# arduino_isp.net
KiCad netlist of a schematic drawn in EAGLE
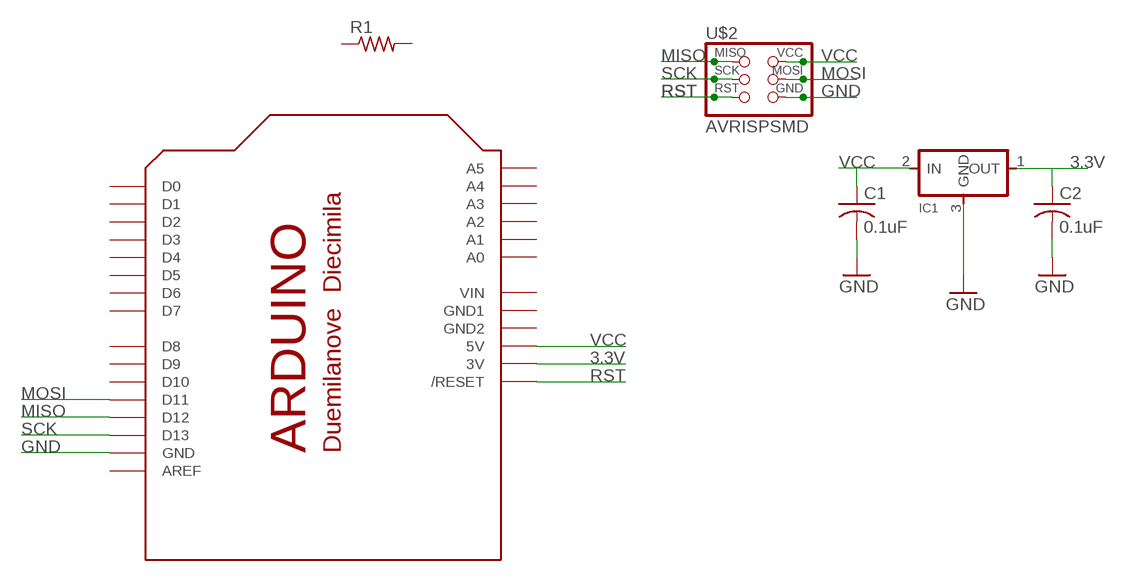
[diagram p0: schematic, sheet 1]

(export (version "E")
  (design (tool "Eeschema 10.0.6"))
  (components
    (comp (ref "C1")
      (value "0.1uF")
      (footprint "eagle-import:C1206")
      (libsource (lib "eagle-import") (part "C-USC1206"))
    )
    (comp (ref "C2")
      (value "0.1uF")
      (footprint "eagle-import:C1206")
      (libsource (lib "eagle-import") (part "C-USC1206"))
    )
    (comp (ref "IC1")
      (value "REGULATORSOT23")
      (footprint "eagle-import:SOT23")
      (libsource (lib "eagle-import") (part "REGULATORSOT23"))
    )
    (comp (ref "R1")
      (value "R-US_M1206")
      (footprint "eagle-import:M1206")
      (libsource (lib "eagle-import") (part "R-US_M1206"))
    )
    (comp (ref "U$1")
      (value "ARDUINODUEMILANOVE")
      (footprint "eagle-import:ARDUINO")
      (libsource (lib "eagle-import") (part "ARDUINODUEMILANOVE"))
    )
    (comp (ref "U$2")
      (value "AVRISPSMD")
      (footprint "eagle-import:2X03SMD")
      (libsource (lib "eagle-import") (part "AVRISPSMD"))
    )
  )
  (nets
    (net (code "1") (name "/3.3V") (class "Default")
      (node (ref "C2") (pin "1") (pinfunction "1_1") (pintype "passive"))
      (node (ref "IC1") (pin "1") (pinfunction "OUT_1") (pintype "bidirectional"))
      (node (ref "U$1") (pin "3V") (pinfunction "3V_3V") (pintype "power_in"))
    )
    (net (code "2") (name "/GND1") (class "Default")
      (node (ref "U$1") (pin "GND1") (pinfunction "GND1_GND1") (pintype "power_in"))
    )
    (net (code "3") (name "/GND2") (class "Default")
      (node (ref "U$1") (pin "GND2") (pinfunction "GND2_GND2") (pintype "power_in"))
    )
    (net (code "4") (name "/MISO") (class "Default")
      (node (ref "U$1") (pin "D12") (pinfunction "D12_D12") (pintype "bidirectional"))
      (node (ref "U$2") (pin "1") (pinfunction "MISO_1") (pintype "passive"))
    )
    (net (code "5") (name "/MOSI") (class "Default")
      (node (ref "U$1") (pin "D11") (pinfunction "D11_D11") (pintype "bidirectional"))
      (node (ref "U$2") (pin "4") (pinfunction "MOSI_4") (pintype "passive"))
    )
    (net (code "6") (name "/RST") (class "Default")
      (node (ref "U$1") (pin "RESET") (pinfunction "/RESET_RESET") (pintype "bidirectional"))
      (node (ref "U$2") (pin "5") (pinfunction "RST_5") (pintype "passive"))
    )
    (net (code "7") (name "/SCK") (class "Default")
      (node (ref "U$1") (pin "D13") (pinfunction "D13_D13") (pintype "bidirectional"))
      (node (ref "U$2") (pin "3") (pinfunction "SCK_3") (pintype "passive"))
    )
    (net (code "8") (name "/VCC") (class "Default")
      (node (ref "C1") (pin "1") (pinfunction "1_1") (pintype "passive"))
      (node (ref "IC1") (pin "2") (pinfunction "IN_2") (pintype "bidirectional"))
      (node (ref "U$1") (pin "5V") (pinfunction "5V_5V") (pintype "power_in"))
      (node (ref "U$2") (pin "2") (pinfunction "VCC_2") (pintype "passive"))
    )
    (net (code "9") (name "/VIN") (class "Default")
      (node (ref "U$1") (pin "VIN") (pinfunction "VIN_VIN") (pintype "power_in"))
    )
    (net (code "10") (name "GND") (class "Default")
      (node (ref "C1") (pin "2") (pinfunction "2_2") (pintype "passive"))
      (node (ref "C2") (pin "2") (pinfunction "2_2") (pintype "passive"))
      (node (ref "IC1") (pin "3") (pinfunction "GND_3") (pintype "bidirectional"))
      (node (ref "U$1") (pin "GND") (pinfunction "GND_GND") (pintype "power_in"))
      (node (ref "U$2") (pin "6") (pinfunction "GND_6") (pintype "passive"))
    )
    (net (code "11") (name "unconnected-(R1-Pad1)") (class "Default")
      (node (ref "R1") (pin "1") (pinfunction "1_1") (pintype "passive"))
    )
    (net (code "12") (name "unconnected-(R1-Pad2)") (class "Default")
      (node (ref "R1") (pin "2") (pinfunction "2_2") (pintype "passive"))
    )
    (net (code "13") (name "unconnected-(U$1-PadA0)") (class "Default")
      (node (ref "U$1") (pin "A0") (pinfunction "A0_A0") (pintype "bidirectional"))
    )
    (net (code "14") (name "unconnected-(U$1-PadA1)") (class "Default")
      (node (ref "U$1") (pin "A1") (pinfunction "A1_A1") (pintype "bidirectional"))
    )
    (net (code "15") (name "unconnected-(U$1-PadA2)") (class "Default")
      (node (ref "U$1") (pin "A2") (pinfunction "A2_A2") (pintype "bidirectional"))
    )
    (net (code "16") (name "unconnected-(U$1-PadA3)") (class "Default")
      (node (ref "U$1") (pin "A3") (pinfunction "A3_A3") (pintype "bidirectional"))
    )
    (net (code "17") (name "unconnected-(U$1-PadA4)") (class "Default")
      (node (ref "U$1") (pin "A4") (pinfunction "A4_A4") (pintype "bidirectional"))
    )
    (net (code "18") (name "unconnected-(U$1-PadA5)") (class "Default")
      (node (ref "U$1") (pin "A5") (pinfunction "A5_A5") (pintype "bidirectional"))
    )
    (net (code "19") (name "unconnected-(U$1-PadAREF)") (class "Default")
      (node (ref "U$1") (pin "AREF") (pinfunction "AREF_AREF") (pintype "bidirectional"))
    )
    (net (code "20") (name "unconnected-(U$1-PadD0)") (class "Default")
      (node (ref "U$1") (pin "D0") (pinfunction "D0_D0") (pintype "bidirectional"))
    )
    (net (code "21") (name "unconnected-(U$1-PadD1)") (class "Default")
      (node (ref "U$1") (pin "D1") (pinfunction "D1_D1") (pintype "bidirectional"))
    )
    (net (code "22") (name "unconnected-(U$1-PadD2)") (class "Default")
      (node (ref "U$1") (pin "D2") (pinfunction "D2_D2") (pintype "bidirectional"))
    )
    (net (code "23") (name "unconnected-(U$1-PadD3)") (class "Default")
      (node (ref "U$1") (pin "D3") (pinfunction "D3_D3") (pintype "bidirectional"))
    )
    (net (code "24") (name "unconnected-(U$1-PadD4)") (class "Default")
      (node (ref "U$1") (pin "D4") (pinfunction "D4_D4") (pintype "bidirectional"))
    )
    (net (code "25") (name "unconnected-(U$1-PadD5)") (class "Default")
      (node (ref "U$1") (pin "D5") (pinfunction "D5_D5") (pintype "bidirectional"))
    )
    (net (code "26") (name "unconnected-(U$1-PadD6)") (class "Default")
      (node (ref "U$1") (pin "D6") (pinfunction "D6_D6") (pintype "bidirectional"))
    )
    (net (code "27") (name "unconnected-(U$1-PadD7)") (class "Default")
      (node (ref "U$1") (pin "D7") (pinfunction "D7_D7") (pintype "bidirectional"))
    )
    (net (code "28") (name "unconnected-(U$1-PadD8)") (class "Default")
      (node (ref "U$1") (pin "D8") (pinfunction "D8_D8") (pintype "bidirectional"))
    )
    (net (code "29") (name "unconnected-(U$1-PadD9)") (class "Default")
      (node (ref "U$1") (pin "D9") (pinfunction "D9_D9") (pintype "bidirectional"))
    )
    (net (code "30") (name "unconnected-(U$1-PadD10)") (class "Default")
      (node (ref "U$1") (pin "D10") (pinfunction "D10_D10") (pintype "bidirectional"))
    )
  )
)
